# SPosition.net
KiCad netlist of a schematic drawn in EAGLE
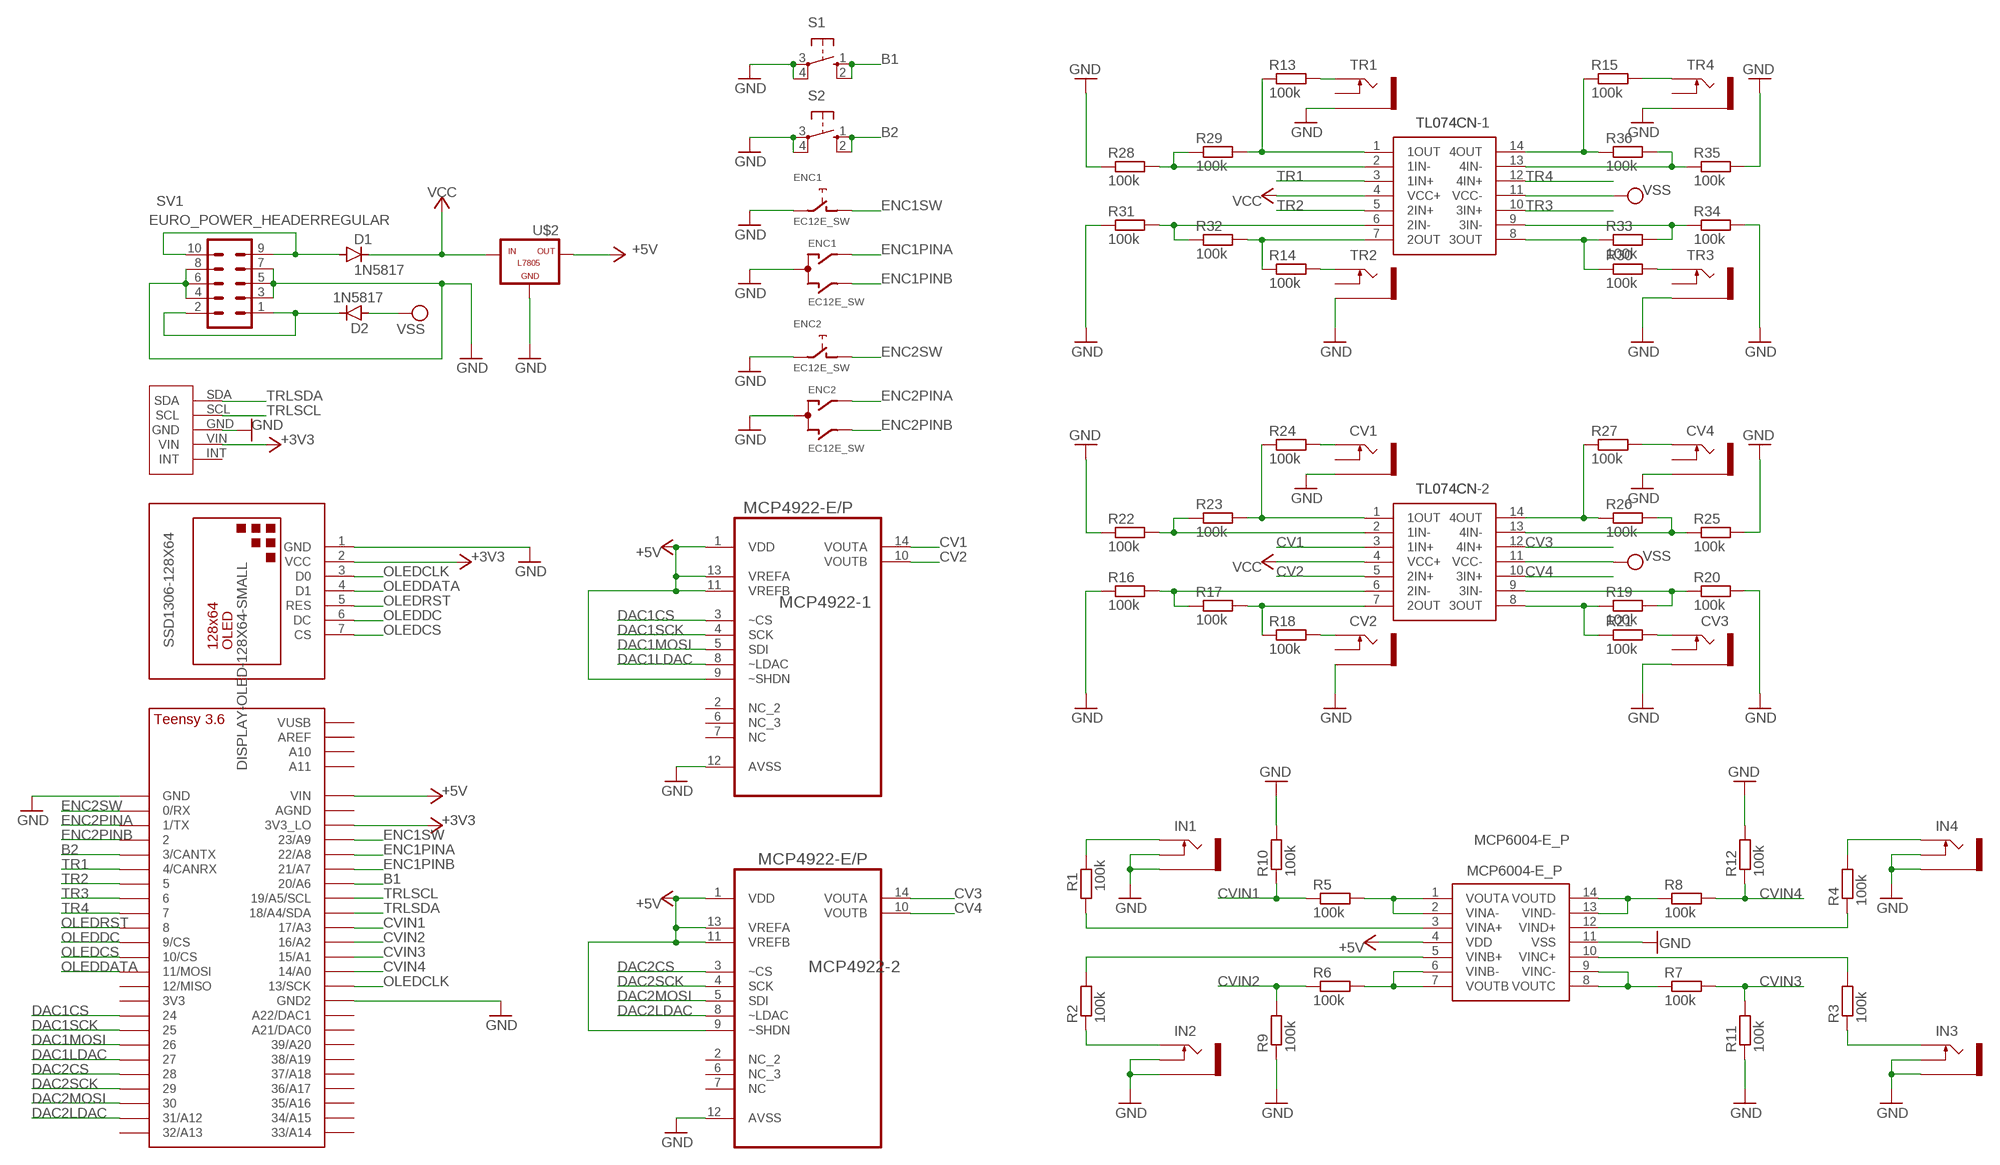
[diagram p0: schematic, sheet 1]

(export (version "E")
  (design (tool "Eeschema 10.0.6"))
  (components
    (comp (ref "CV1")
      (value "THONKICONNNEW")
      (footprint "eagle-import:WQP-PJ301M-12_JACK")
      (libsource (lib "eagle-import") (part "THONKICONNNEW"))
    )
    (comp (ref "CV2")
      (value "THONKICONNNEW")
      (footprint "eagle-import:WQP-PJ301M-12_JACK")
      (libsource (lib "eagle-import") (part "THONKICONNNEW"))
    )
    (comp (ref "CV3")
      (value "THONKICONNNEW")
      (footprint "eagle-import:WQP-PJ301M-12_JACK")
      (libsource (lib "eagle-import") (part "THONKICONNNEW"))
    )
    (comp (ref "CV4")
      (value "THONKICONNNEW")
      (footprint "eagle-import:WQP-PJ301M-12_JACK")
      (libsource (lib "eagle-import") (part "THONKICONNNEW"))
    )
    (comp (ref "D1")
      (value "1N5817")
      (footprint "eagle-import:DO41-10")
      (libsource (lib "eagle-import") (part "1N4004"))
    )
    (comp (ref "D2")
      (value "1N5817")
      (footprint "eagle-import:DO41-10")
      (libsource (lib "eagle-import") (part "1N4004"))
    )
    (comp (ref "ENC1")
      (value "EC12E_SW")
      (footprint "eagle-import:ALPS_EC12E_SW")
      (fields (field (name "MPN") "EC12E2424407"))
      (libsource (lib "eagle-import") (part "EC12E_SW"))
    )
    (comp (ref "ENC2")
      (value "EC12E_SW")
      (footprint "eagle-import:ALPS_EC12E_SW")
      (fields (field (name "MPN") "EC12E2424407"))
      (libsource (lib "eagle-import") (part "EC12E_SW"))
    )
    (comp (ref "IN1")
      (value "THONKICONNNEW")
      (footprint "eagle-import:WQP-PJ301M-12_JACK")
      (libsource (lib "eagle-import") (part "THONKICONNNEW"))
    )
    (comp (ref "IN2")
      (value "THONKICONNNEW")
      (footprint "eagle-import:WQP-PJ301M-12_JACK")
      (libsource (lib "eagle-import") (part "THONKICONNNEW"))
    )
    (comp (ref "IN3")
      (value "THONKICONNNEW")
      (footprint "eagle-import:WQP-PJ301M-12_JACK")
      (libsource (lib "eagle-import") (part "THONKICONNNEW"))
    )
    (comp (ref "IN4")
      (value "THONKICONNNEW")
      (footprint "eagle-import:WQP-PJ301M-12_JACK")
      (libsource (lib "eagle-import") (part "THONKICONNNEW"))
    )
    (comp (ref "MCP4922-1")
      (value "MCP4922-E/P")
      (footprint "eagle-import:DIP254P762X533-14")
      (fields (field (name "MF") "Microchip"))
      (libsource (lib "eagle-import") (part "MCP4922-E/P"))
    )
    (comp (ref "MCP4922-2")
      (value "MCP4922-E/P")
      (footprint "eagle-import:DIP254P762X533-14")
      (fields (field (name "MF") "Microchip"))
      (libsource (lib "eagle-import") (part "MCP4922-E/P"))
    )
    (comp (ref "MCP6004-E_P")
      (value "MCP6004-E_P")
      (footprint "eagle-import:DIP781W56P254L1918H533Q14N")
      (fields
        (field (name "MANUFACTURER_PART_NUMBER") "mcp6004-e/p")
        (field (name "MOUSER_PART_NUMBER") "579-MCP6004-E/P")
        (field (name "RS_PART_NUMBER") "7386178P")
      )
      (libsource (lib "eagle-import") (part "MCP6004-E_P"))
    )
    (comp (ref "R1")
      (value "100k")
      (footprint "eagle-import:R0805")
      (libsource (lib "eagle-import") (part "R-EU_R0805"))
    )
    (comp (ref "R2")
      (value "100k")
      (footprint "eagle-import:R0805")
      (libsource (lib "eagle-import") (part "R-EU_R0805"))
    )
    (comp (ref "R3")
      (value "100k")
      (footprint "eagle-import:R0805")
      (libsource (lib "eagle-import") (part "R-EU_R0805"))
    )
    (comp (ref "R4")
      (value "100k")
      (footprint "eagle-import:R0805")
      (libsource (lib "eagle-import") (part "R-EU_R0805"))
    )
    (comp (ref "R5")
      (value "100k")
      (footprint "eagle-import:R0805")
      (libsource (lib "eagle-import") (part "R-EU_R0805"))
    )
    (comp (ref "R6")
      (value "100k")
      (footprint "eagle-import:R0805")
      (libsource (lib "eagle-import") (part "R-EU_R0805"))
    )
    (comp (ref "R7")
      (value "100k")
      (footprint "eagle-import:R0805")
      (libsource (lib "eagle-import") (part "R-EU_R0805"))
    )
    (comp (ref "R8")
      (value "100k")
      (footprint "eagle-import:R0805")
      (libsource (lib "eagle-import") (part "R-EU_R0805"))
    )
    (comp (ref "R9")
      (value "100k")
      (footprint "eagle-import:R0805")
      (libsource (lib "eagle-import") (part "R-EU_R0805"))
    )
    (comp (ref "R10")
      (value "100k")
      (footprint "eagle-import:R0805")
      (libsource (lib "eagle-import") (part "R-EU_R0805"))
    )
    (comp (ref "R11")
      (value "100k")
      (footprint "eagle-import:R0805")
      (libsource (lib "eagle-import") (part "R-EU_R0805"))
    )
    (comp (ref "R12")
      (value "100k")
      (footprint "eagle-import:R0805")
      (libsource (lib "eagle-import") (part "R-EU_R0805"))
    )
    (comp (ref "R13")
      (value "100k")
      (footprint "eagle-import:R0805")
      (libsource (lib "eagle-import") (part "R-EU_R0805"))
    )
    (comp (ref "R14")
      (value "100k")
      (footprint "eagle-import:R0805")
      (libsource (lib "eagle-import") (part "R-EU_R0805"))
    )
    (comp (ref "R15")
      (value "100k")
      (footprint "eagle-import:R0805")
      (libsource (lib "eagle-import") (part "R-EU_R0805"))
    )
    (comp (ref "R16")
      (value "100k")
      (footprint "eagle-import:R0805")
      (libsource (lib "eagle-import") (part "R-EU_R0805"))
    )
    (comp (ref "R17")
      (value "100k")
      (footprint "eagle-import:R0805")
      (libsource (lib "eagle-import") (part "R-EU_R0805"))
    )
    (comp (ref "R18")
      (value "100k")
      (footprint "eagle-import:R0805")
      (libsource (lib "eagle-import") (part "R-EU_R0805"))
    )
    (comp (ref "R19")
      (value "100k")
      (footprint "eagle-import:R0805")
      (libsource (lib "eagle-import") (part "R-EU_R0805"))
    )
    (comp (ref "R20")
      (value "100k")
      (footprint "eagle-import:R0805")
      (libsource (lib "eagle-import") (part "R-EU_R0805"))
    )
    (comp (ref "R21")
      (value "100k")
      (footprint "eagle-import:R0805")
      (libsource (lib "eagle-import") (part "R-EU_R0805"))
    )
    (comp (ref "R22")
      (value "100k")
      (footprint "eagle-import:R0805")
      (libsource (lib "eagle-import") (part "R-EU_R0805"))
    )
    (comp (ref "R23")
      (value "100k")
      (footprint "eagle-import:R0805")
      (libsource (lib "eagle-import") (part "R-EU_R0805"))
    )
    (comp (ref "R24")
      (value "100k")
      (footprint "eagle-import:R0805")
      (libsource (lib "eagle-import") (part "R-EU_R0805"))
    )
    (comp (ref "R25")
      (value "100k")
      (footprint "eagle-import:R0805")
      (libsource (lib "eagle-import") (part "R-EU_R0805"))
    )
    (comp (ref "R26")
      (value "100k")
      (footprint "eagle-import:R0805")
      (libsource (lib "eagle-import") (part "R-EU_R0805"))
    )
    (comp (ref "R27")
      (value "100k")
      (footprint "eagle-import:R0805")
      (libsource (lib "eagle-import") (part "R-EU_R0805"))
    )
    (comp (ref "R28")
      (value "100k")
      (footprint "eagle-import:R0805")
      (libsource (lib "eagle-import") (part "R-EU_R0805"))
    )
    (comp (ref "R29")
      (value "100k")
      (footprint "eagle-import:R0805")
      (libsource (lib "eagle-import") (part "R-EU_R0805"))
    )
    (comp (ref "R30")
      (value "100k")
      (footprint "eagle-import:R0805")
      (libsource (lib "eagle-import") (part "R-EU_R0805"))
    )
    (comp (ref "R31")
      (value "100k")
      (footprint "eagle-import:R0805")
      (libsource (lib "eagle-import") (part "R-EU_R0805"))
    )
    (comp (ref "R32")
      (value "100k")
      (footprint "eagle-import:R0805")
      (libsource (lib "eagle-import") (part "R-EU_R0805"))
    )
    (comp (ref "R33")
      (value "100k")
      (footprint "eagle-import:R0805")
      (libsource (lib "eagle-import") (part "R-EU_R0805"))
    )
    (comp (ref "R34")
      (value "100k")
      (footprint "eagle-import:R0805")
      (libsource (lib "eagle-import") (part "R-EU_R0805"))
    )
    (comp (ref "R35")
      (value "100k")
      (footprint "eagle-import:R0805")
      (libsource (lib "eagle-import") (part "R-EU_R0805"))
    )
    (comp (ref "R36")
      (value "100k")
      (footprint "eagle-import:R0805")
      (libsource (lib "eagle-import") (part "R-EU_R0805"))
    )
    (comp (ref "S1")
      (value "10-XX")
      (footprint "eagle-import:B3F-10XX")
      (fields (field (name "MPN") "B3F-1000"))
      (libsource (lib "eagle-import") (part "10-XX"))
    )
    (comp (ref "S2")
      (value "10-XX")
      (footprint "eagle-import:B3F-10XX")
      (fields (field (name "MPN") "B3F-1000"))
      (libsource (lib "eagle-import") (part "10-XX"))
    )
    (comp (ref "SSD1306-128X64")
      (value "DISPLAY-OLED-128X64-SMALL")
      (footprint "eagle-import:DISPLAY-OLED-128X64-SMALL")
      (libsource (lib "eagle-import") (part "DISPLAY-OLED-128X64-SMALL"))
    )
    (comp (ref "SV1")
      (value "EURO_POWER_HEADERREGULAR")
      (footprint "eagle-import:EURO_POWER_HEADER")
      (libsource (lib "eagle-import") (part "EURO_POWER_HEADERREGULAR"))
    )
    (comp (ref "TL074CN-1")
      (value "TL074CN")
      (footprint "eagle-import:DIP794W53P254L1930H508Q14N")
      (fields (field (name "MOUSER_PART_NUMBER") "595-TL074CN") (field (name "RS_PART_NUMBER") "0302621P"))
      (libsource (lib "eagle-import") (part "TL074CN"))
    )
    (comp (ref "TL074CN-2")
      (value "TL074CN")
      (footprint "eagle-import:DIP794W53P254L1930H508Q14N")
      (fields (field (name "MOUSER_PART_NUMBER") "595-TL074CN") (field (name "RS_PART_NUMBER") "0302621P"))
      (libsource (lib "eagle-import") (part "TL074CN"))
    )
    (comp (ref "TR1")
      (value "THONKICONNNEW")
      (footprint "eagle-import:WQP-PJ301M-12_JACK")
      (libsource (lib "eagle-import") (part "THONKICONNNEW"))
    )
    (comp (ref "TR2")
      (value "THONKICONNNEW")
      (footprint "eagle-import:WQP-PJ301M-12_JACK")
      (libsource (lib "eagle-import") (part "THONKICONNNEW"))
    )
    (comp (ref "TR3")
      (value "THONKICONNNEW")
      (footprint "eagle-import:WQP-PJ301M-12_JACK")
      (libsource (lib "eagle-import") (part "THONKICONNNEW"))
    )
    (comp (ref "TR4")
      (value "THONKICONNNEW")
      (footprint "eagle-import:WQP-PJ301M-12_JACK")
      (libsource (lib "eagle-import") (part "THONKICONNNEW"))
    )
    (comp (ref "U$1")
      (value "TEENSY_3.5/3.6_BASIC")
      (footprint "eagle-import:TEENSY_3.5_3.6_BASIC")
      (libsource (lib "eagle-import") (part "TEENSY_3.5/3.6_BASIC"))
    )
    (comp (ref "U$2")
      (value "-L7805")
      (footprint "eagle-import:L7805")
      (libsource (lib "eagle-import") (part "-L7805"))
    )
    (comp (ref "U$4")
      (value "SPREV3")
      (footprint "eagle-import:SPREV3")
      (libsource (lib "eagle-import") (part "SPREV3"))
    )
  )
  (nets
    (net (code "1") (name "+3V3") (class "Default")
      (node (ref "SSD1306-128X64") (pin "2") (pinfunction "VCC_2") (pintype "power_in"))
      (node (ref "U$1") (pin "3V3_LO") (pinfunction "3V3_LO_3V3_LO") (pintype "bidirectional"))
      (node (ref "U$4") (pin "VIN") (pinfunction "VIN_VIN") (pintype "bidirectional"))
    )
    (net (code "2") (name "+5V") (class "Default")
      (node (ref "MCP4922-1") (pin "1") (pinfunction "VDD_1") (pintype "power_in"))
      (node (ref "MCP4922-1") (pin "11") (pinfunction "VREFB_11") (pintype "input"))
      (node (ref "MCP4922-1") (pin "13") (pinfunction "VREFA_13") (pintype "input"))
      (node (ref "MCP4922-1") (pin "9") (pinfunction "~{SHDN}_9") (pintype "input"))
      (node (ref "MCP4922-2") (pin "1") (pinfunction "VDD_1") (pintype "power_in"))
      (node (ref "MCP4922-2") (pin "11") (pinfunction "VREFB_11") (pintype "input"))
      (node (ref "MCP4922-2") (pin "13") (pinfunction "VREFA_13") (pintype "input"))
      (node (ref "MCP4922-2") (pin "9") (pinfunction "~{SHDN}_9") (pintype "input"))
      (node (ref "MCP6004-E_P") (pin "4") (pinfunction "VDD_4") (pintype "power_in"))
      (node (ref "U$1") (pin "VIN") (pinfunction "VIN_VIN") (pintype "bidirectional"))
      (node (ref "U$2") (pin "OUT") (pinfunction "OUT_OUT") (pintype "passive"))
    )
    (net (code "3") (name "/B1") (class "Default")
      (node (ref "S1") (pin "1") (pinfunction "S_1") (pintype "passive"))
      (node (ref "S1") (pin "2") (pinfunction "S1_2") (pintype "passive"))
      (node (ref "U$1") (pin "20/A6") (pinfunction "20/A6_20/A6") (pintype "bidirectional"))
    )
    (net (code "4") (name "/B2") (class "Default")
      (node (ref "S2") (pin "1") (pinfunction "S_1") (pintype "passive"))
      (node (ref "S2") (pin "2") (pinfunction "S1_2") (pintype "passive"))
      (node (ref "U$1") (pin "3/CANTX") (pinfunction "3/CANTX_3/CANTX") (pintype "bidirectional"))
    )
    (net (code "5") (name "/CV1") (class "Default")
      (node (ref "MCP4922-1") (pin "14") (pinfunction "VOUTA_14") (pintype "output"))
      (node (ref "TL074CN-2") (pin "3") (pinfunction "1IN+_3") (pintype "input"))
    )
    (net (code "6") (name "/CV2") (class "Default")
      (node (ref "MCP4922-1") (pin "10") (pinfunction "VOUTB_10") (pintype "output"))
      (node (ref "TL074CN-2") (pin "5") (pinfunction "2IN+_5") (pintype "input"))
    )
    (net (code "7") (name "/CV3") (class "Default")
      (node (ref "MCP4922-2") (pin "14") (pinfunction "VOUTA_14") (pintype "output"))
      (node (ref "TL074CN-2") (pin "12") (pinfunction "4IN+_12") (pintype "input"))
    )
    (net (code "8") (name "/CV4") (class "Default")
      (node (ref "MCP4922-2") (pin "10") (pinfunction "VOUTB_10") (pintype "output"))
      (node (ref "TL074CN-2") (pin "10") (pinfunction "3IN+_10") (pintype "input"))
    )
    (net (code "9") (name "/CVIN1") (class "Default")
      (node (ref "R10") (pin "1") (pinfunction "1_1") (pintype "passive"))
      (node (ref "R5") (pin "1") (pinfunction "1_1") (pintype "passive"))
      (node (ref "U$1") (pin "17/A3") (pinfunction "17/A3_17/A3") (pintype "bidirectional"))
    )
    (net (code "10") (name "/CVIN2") (class "Default")
      (node (ref "R6") (pin "1") (pinfunction "1_1") (pintype "passive"))
      (node (ref "R9") (pin "2") (pinfunction "2_2") (pintype "passive"))
      (node (ref "U$1") (pin "16/A2") (pinfunction "16/A2_16/A2") (pintype "bidirectional"))
    )
    (net (code "11") (name "/CVIN3") (class "Default")
      (node (ref "R11") (pin "2") (pinfunction "2_2") (pintype "passive"))
      (node (ref "R7") (pin "2") (pinfunction "2_2") (pintype "passive"))
      (node (ref "U$1") (pin "15/A1") (pinfunction "15/A1_15/A1") (pintype "bidirectional"))
    )
    (net (code "12") (name "/CVIN4") (class "Default")
      (node (ref "R12") (pin "1") (pinfunction "1_1") (pintype "passive"))
      (node (ref "R8") (pin "2") (pinfunction "2_2") (pintype "passive"))
      (node (ref "U$1") (pin "14/A0") (pinfunction "14/A0_14/A0") (pintype "bidirectional"))
    )
    (net (code "13") (name "/DAC1CS") (class "Default")
      (node (ref "MCP4922-1") (pin "3") (pinfunction "~{CS}_3") (pintype "input"))
      (node (ref "U$1") (pin "24") (pinfunction "24_24") (pintype "bidirectional"))
    )
    (net (code "14") (name "/DAC1LDAC") (class "Default")
      (node (ref "MCP4922-1") (pin "8") (pinfunction "~{LDAC}_8") (pintype "input"))
      (node (ref "U$1") (pin "27") (pinfunction "27_27") (pintype "bidirectional"))
    )
    (net (code "15") (name "/DAC1MOSI") (class "Default")
      (node (ref "MCP4922-1") (pin "5") (pinfunction "SDI_5") (pintype "input"))
      (node (ref "U$1") (pin "26") (pinfunction "26_26") (pintype "bidirectional"))
    )
    (net (code "16") (name "/DAC1SCK") (class "Default")
      (node (ref "MCP4922-1") (pin "4") (pinfunction "SCK_4") (pintype "input"))
      (node (ref "U$1") (pin "25") (pinfunction "25_25") (pintype "bidirectional"))
    )
    (net (code "17") (name "/DAC2CS") (class "Default")
      (node (ref "MCP4922-2") (pin "3") (pinfunction "~{CS}_3") (pintype "input"))
      (node (ref "U$1") (pin "28") (pinfunction "28_28") (pintype "bidirectional"))
    )
    (net (code "18") (name "/DAC2LDAC") (class "Default")
      (node (ref "MCP4922-2") (pin "8") (pinfunction "~{LDAC}_8") (pintype "input"))
      (node (ref "U$1") (pin "31/A12") (pinfunction "31/A12_31/A12") (pintype "bidirectional"))
    )
    (net (code "19") (name "/DAC2MOSI") (class "Default")
      (node (ref "MCP4922-2") (pin "5") (pinfunction "SDI_5") (pintype "input"))
      (node (ref "U$1") (pin "30") (pinfunction "30_30") (pintype "bidirectional"))
    )
    (net (code "20") (name "/DAC2SCK") (class "Default")
      (node (ref "MCP4922-2") (pin "4") (pinfunction "SCK_4") (pintype "input"))
      (node (ref "U$1") (pin "29") (pinfunction "29_29") (pintype "bidirectional"))
    )
    (net (code "21") (name "/ENC1PINA") (class "Default")
      (node (ref "ENC1") (pin "A") (pinfunction "A_A") (pintype "passive"))
      (node (ref "U$1") (pin "22/A8") (pinfunction "22/A8_22/A8") (pintype "bidirectional"))
    )
    (net (code "22") (name "/ENC1PINB") (class "Default")
      (node (ref "ENC1") (pin "B") (pinfunction "B_B") (pintype "passive"))
      (node (ref "U$1") (pin "21/A7") (pinfunction "21/A7_21/A7") (pintype "bidirectional"))
    )
    (net (code "23") (name "/ENC1SW") (class "Default")
      (node (ref "ENC1") (pin "D") (pinfunction "1_D") (pintype "passive"))
      (node (ref "U$1") (pin "23/A9") (pinfunction "23/A9_23/A9") (pintype "bidirectional"))
    )
    (net (code "24") (name "/ENC2PINA") (class "Default")
      (node (ref "ENC2") (pin "A") (pinfunction "A_A") (pintype "passive"))
      (node (ref "U$1") (pin "1/TX") (pinfunction "1/TX_1/TX") (pintype "bidirectional"))
    )
    (net (code "25") (name "/ENC2PINB") (class "Default")
      (node (ref "ENC2") (pin "B") (pinfunction "B_B") (pintype "passive"))
      (node (ref "U$1") (pin "2") (pinfunction "2_2") (pintype "bidirectional"))
    )
    (net (code "26") (name "/ENC2SW") (class "Default")
      (node (ref "ENC2") (pin "D") (pinfunction "1_D") (pintype "passive"))
      (node (ref "U$1") (pin "0/RX") (pinfunction "0/RX_0/RX") (pintype "bidirectional"))
    )
    (net (code "27") (name "/OLEDCLK") (class "Default")
      (node (ref "SSD1306-128X64") (pin "3") (pinfunction "D0_3") (pintype "bidirectional"))
      (node (ref "U$1") (pin "13/SCK") (pinfunction "13/SCK_13/SCK") (pintype "bidirectional"))
    )
    (net (code "28") (name "/OLEDCS") (class "Default")
      (node (ref "SSD1306-128X64") (pin "7") (pinfunction "CS_7") (pintype "bidirectional"))
      (node (ref "U$1") (pin "10/CS") (pinfunction "10/CS_10/CS") (pintype "bidirectional"))
    )
    (net (code "29") (name "/OLEDDATA") (class "Default")
      (node (ref "SSD1306-128X64") (pin "4") (pinfunction "D1_4") (pintype "bidirectional"))
      (node (ref "U$1") (pin "11/MOSI") (pinfunction "11/MOSI_11/MOSI") (pintype "bidirectional"))
    )
    (net (code "30") (name "/OLEDDC") (class "Default")
      (node (ref "SSD1306-128X64") (pin "6") (pinfunction "DC_6") (pintype "bidirectional"))
      (node (ref "U$1") (pin "9/CS") (pinfunction "9/CS_9/CS") (pintype "bidirectional"))
    )
    (net (code "31") (name "/OLEDRST") (class "Default")
      (node (ref "SSD1306-128X64") (pin "5") (pinfunction "RES_5") (pintype "bidirectional"))
      (node (ref "U$1") (pin "8") (pinfunction "8_8") (pintype "bidirectional"))
    )
    (net (code "32") (name "/TR1") (class "Default")
      (node (ref "TL074CN-1") (pin "3") (pinfunction "1IN+_3") (pintype "input"))
      (node (ref "U$1") (pin "4/CANRX") (pinfunction "4/CANRX_4/CANRX") (pintype "bidirectional"))
    )
    (net (code "33") (name "/TR2") (class "Default")
      (node (ref "TL074CN-1") (pin "5") (pinfunction "2IN+_5") (pintype "input"))
      (node (ref "U$1") (pin "5") (pinfunction "5_5") (pintype "bidirectional"))
    )
    (net (code "34") (name "/TR3") (class "Default")
      (node (ref "TL074CN-1") (pin "10") (pinfunction "3IN+_10") (pintype "input"))
      (node (ref "U$1") (pin "6") (pinfunction "6_6") (pintype "bidirectional"))
    )
    (net (code "35") (name "/TR4") (class "Default")
      (node (ref "TL074CN-1") (pin "12") (pinfunction "4IN+_12") (pintype "input"))
      (node (ref "U$1") (pin "7") (pinfunction "7_7") (pintype "bidirectional"))
    )
    (net (code "36") (name "/TRLSCL") (class "Default")
      (node (ref "U$1") (pin "19/A5/SCL") (pinfunction "19/A5/SCL_19/A5/SCL") (pintype "bidirectional"))
      (node (ref "U$4") (pin "SCL") (pinfunction "SCL_SCL") (pintype "bidirectional"))
    )
    (net (code "37") (name "/TRLSDA") (class "Default")
      (node (ref "U$1") (pin "18/A4/SDA") (pinfunction "18/A4/SDA_18/A4/SDA") (pintype "bidirectional"))
      (node (ref "U$4") (pin "SDA") (pinfunction "SDA_SDA") (pintype "bidirectional"))
    )
    (net (code "38") (name "GND") (class "Default")
      (node (ref "CV1") (pin "P$3_SLEEVE") (pinfunction "SLEEVE_P$3_SLEEVE") (pintype "passive"))
      (node (ref "CV2") (pin "P$3_SLEEVE") (pinfunction "SLEEVE_P$3_SLEEVE") (pintype "passive"))
      (node (ref "CV3") (pin "P$3_SLEEVE") (pinfunction "SLEEVE_P$3_SLEEVE") (pintype "passive"))
      (node (ref "CV4") (pin "P$3_SLEEVE") (pinfunction "SLEEVE_P$3_SLEEVE") (pintype "passive"))
      (node (ref "ENC1") (pin "C") (pinfunction "C_C") (pintype "passive"))
      (node (ref "ENC1") (pin "E") (pinfunction "2_E") (pintype "passive"))
      (node (ref "ENC2") (pin "C") (pinfunction "C_C") (pintype "passive"))
      (node (ref "ENC2") (pin "E") (pinfunction "2_E") (pintype "passive"))
      (node (ref "IN1") (pin "P$2_SWITCH") (pinfunction "SWITCH_P$2_SWITCH") (pintype "passive"))
      (node (ref "IN1") (pin "P$3_SLEEVE") (pinfunction "SLEEVE_P$3_SLEEVE") (pintype "passive"))
      (node (ref "IN2") (pin "P$2_SWITCH") (pinfunction "SWITCH_P$2_SWITCH") (pintype "passive"))
      (node (ref "IN2") (pin "P$3_SLEEVE") (pinfunction "SLEEVE_P$3_SLEEVE") (pintype "passive"))
      (node (ref "IN3") (pin "P$2_SWITCH") (pinfunction "SWITCH_P$2_SWITCH") (pintype "passive"))
      (node (ref "IN3") (pin "P$3_SLEEVE") (pinfunction "SLEEVE_P$3_SLEEVE") (pintype "passive"))
      (node (ref "IN4") (pin "P$2_SWITCH") (pinfunction "SWITCH_P$2_SWITCH") (pintype "passive"))
      (node (ref "IN4") (pin "P$3_SLEEVE") (pinfunction "SLEEVE_P$3_SLEEVE") (pintype "passive"))
      (node (ref "MCP4922-1") (pin "12") (pinfunction "AVSS_12") (pintype "power_in"))
      (node (ref "MCP4922-2") (pin "12") (pinfunction "AVSS_12") (pintype "power_in"))
      (node (ref "MCP6004-E_P") (pin "11") (pinfunction "VSS_11") (pintype "power_in"))
      (node (ref "R10") (pin "2") (pinfunction "2_2") (pintype "passive"))
      (node (ref "R11") (pin "1") (pinfunction "1_1") (pintype "passive"))
      (node (ref "R12") (pin "2") (pinfunction "2_2") (pintype "passive"))
      (node (ref "R16") (pin "1") (pinfunction "1_1") (pintype "passive"))
      (node (ref "R20") (pin "2") (pinfunction "2_2") (pintype "passive"))
      (node (ref "R22") (pin "1") (pinfunction "1_1") (pintype "passive"))
      (node (ref "R25") (pin "2") (pinfunction "2_2") (pintype "passive"))
      (node (ref "R28") (pin "1") (pinfunction "1_1") (pintype "passive"))
      (node (ref "R31") (pin "1") (pinfunction "1_1") (pintype "passive"))
      (node (ref "R34") (pin "2") (pinfunction "2_2") (pintype "passive"))
      (node (ref "R35") (pin "2") (pinfunction "2_2") (pintype "passive"))
      (node (ref "R9") (pin "1") (pinfunction "1_1") (pintype "passive"))
      (node (ref "S1") (pin "3") (pinfunction "P_3") (pintype "passive"))
      (node (ref "S1") (pin "4") (pinfunction "P1_4") (pintype "passive"))
      (node (ref "S2") (pin "3") (pinfunction "P_3") (pintype "passive"))
      (node (ref "S2") (pin "4") (pinfunction "P1_4") (pintype "passive"))
      (node (ref "SSD1306-128X64") (pin "1") (pinfunction "GND_1") (pintype "power_in"))
      (node (ref "SV1") (pin "3") (pinfunction "3_3") (pintype "passive"))
      (node (ref "SV1") (pin "4") (pinfunction "4_4") (pintype "passive"))
      (node (ref "SV1") (pin "5") (pinfunction "5_5") (pintype "passive"))
      (node (ref "SV1") (pin "6") (pinfunction "6_6") (pintype "passive"))
      (node (ref "SV1") (pin "7") (pinfunction "7_7") (pintype "passive"))
      (node (ref "SV1") (pin "8") (pinfunction "8_8") (pintype "passive"))
      (node (ref "TR1") (pin "P$3_SLEEVE") (pinfunction "SLEEVE_P$3_SLEEVE") (pintype "passive"))
      (node (ref "TR2") (pin "P$3_SLEEVE") (pinfunction "SLEEVE_P$3_SLEEVE") (pintype "passive"))
      (node (ref "TR3") (pin "P$3_SLEEVE") (pinfunction "SLEEVE_P$3_SLEEVE") (pintype "passive"))
      (node (ref "TR4") (pin "P$3_SLEEVE") (pinfunction "SLEEVE_P$3_SLEEVE") (pintype "passive"))
      (node (ref "U$1") (pin "GND") (pinfunction "GND_GND") (pintype "bidirectional"))
      (node (ref "U$1") (pin "GND2") (pinfunction "GND2_GND2") (pintype "bidirectional"))
      (node (ref "U$2") (pin "GND") (pinfunction "GND_GND") (pintype "input"))
      (node (ref "U$4") (pin "GND") (pinfunction "GND_GND") (pintype "bidirectional"))
    )
    (net (code "39") (name "Net-(CV1-TIP)") (class "Default")
      (node (ref "CV1") (pin "P$1_TIP") (pinfunction "TIP_P$1_TIP") (pintype "passive"))
      (node (ref "R24") (pin "2") (pinfunction "2_2") (pintype "passive"))
    )
    (net (code "40") (name "Net-(CV2-TIP)") (class "Default")
      (node (ref "CV2") (pin "P$1_TIP") (pinfunction "TIP_P$1_TIP") (pintype "passive"))
      (node (ref "R18") (pin "2") (pinfunction "2_2") (pintype "passive"))
    )
    (net (code "41") (name "Net-(CV3-TIP)") (class "Default")
      (node (ref "CV3") (pin "P$1_TIP") (pinfunction "TIP_P$1_TIP") (pintype "passive"))
      (node (ref "R21") (pin "2") (pinfunction "2_2") (pintype "passive"))
    )
    (net (code "42") (name "Net-(CV4-TIP)") (class "Default")
      (node (ref "CV4") (pin "P$1_TIP") (pinfunction "TIP_P$1_TIP") (pintype "passive"))
      (node (ref "R27") (pin "2") (pinfunction "2_2") (pintype "passive"))
    )
    (net (code "43") (name "Net-(D1-PadA)") (class "Default")
      (node (ref "D1") (pin "A") (pinfunction "A_A") (pintype "passive"))
      (node (ref "SV1") (pin "10") (pinfunction "10_10") (pintype "passive"))
      (node (ref "SV1") (pin "9") (pinfunction "9_9") (pintype "passive"))
    )
    (net (code "44") (name "Net-(D2-PadC)") (class "Default")
      (node (ref "D2") (pin "C") (pinfunction "C_C") (pintype "passive"))
      (node (ref "SV1") (pin "1") (pinfunction "1_1") (pintype "passive"))
      (node (ref "SV1") (pin "2") (pinfunction "2_2") (pintype "passive"))
    )
    (net (code "45") (name "Net-(IN1-TIP)") (class "Default")
      (node (ref "IN1") (pin "P$1_TIP") (pinfunction "TIP_P$1_TIP") (pintype "passive"))
      (node (ref "R1") (pin "2") (pinfunction "2_2") (pintype "passive"))
    )
    (net (code "46") (name "Net-(IN2-TIP)") (class "Default")
      (node (ref "IN2") (pin "P$1_TIP") (pinfunction "TIP_P$1_TIP") (pintype "passive"))
      (node (ref "R2") (pin "1") (pinfunction "1_1") (pintype "passive"))
    )
    (net (code "47") (name "Net-(IN3-TIP)") (class "Default")
      (node (ref "IN3") (pin "P$1_TIP") (pinfunction "TIP_P$1_TIP") (pintype "passive"))
      (node (ref "R3") (pin "1") (pinfunction "1_1") (pintype "passive"))
    )
    (net (code "48") (name "Net-(IN4-TIP)") (class "Default")
      (node (ref "IN4") (pin "P$1_TIP") (pinfunction "TIP_P$1_TIP") (pintype "passive"))
      (node (ref "R4") (pin "2") (pinfunction "2_2") (pintype "passive"))
    )
    (net (code "49") (name "Net-(MCP6004-E_P-VINA+)") (class "Default")
      (node (ref "MCP6004-E_P") (pin "3") (pinfunction "VINA+_3") (pintype "input"))
      (node (ref "R1") (pin "1") (pinfunction "1_1") (pintype "passive"))
    )
    (net (code "50") (name "Net-(MCP6004-E_P-VINA-)") (class "Default")
      (node (ref "MCP6004-E_P") (pin "1") (pinfunction "VOUTA_1") (pintype "output"))
      (node (ref "MCP6004-E_P") (pin "2") (pinfunction "VINA-_2") (pintype "input"))
      (node (ref "R5") (pin "2") (pinfunction "2_2") (pintype "passive"))
    )
    (net (code "51") (name "Net-(MCP6004-E_P-VINB+)") (class "Default")
      (node (ref "MCP6004-E_P") (pin "5") (pinfunction "VINB+_5") (pintype "input"))
      (node (ref "R2") (pin "2") (pinfunction "2_2") (pintype "passive"))
    )
    (net (code "52") (name "Net-(MCP6004-E_P-VINB-)") (class "Default")
      (node (ref "MCP6004-E_P") (pin "6") (pinfunction "VINB-_6") (pintype "input"))
      (node (ref "MCP6004-E_P") (pin "7") (pinfunction "VOUTB_7") (pintype "output"))
      (node (ref "R6") (pin "2") (pinfunction "2_2") (pintype "passive"))
    )
    (net (code "53") (name "Net-(MCP6004-E_P-VINC+)") (class "Default")
      (node (ref "MCP6004-E_P") (pin "10") (pinfunction "VINC+_10") (pintype "input"))
      (node (ref "R3") (pin "2") (pinfunction "2_2") (pintype "passive"))
    )
    (net (code "54") (name "Net-(MCP6004-E_P-VINC-)") (class "Default")
      (node (ref "MCP6004-E_P") (pin "8") (pinfunction "VOUTC_8") (pintype "output"))
      (node (ref "MCP6004-E_P") (pin "9") (pinfunction "VINC-_9") (pintype "input"))
      (node (ref "R7") (pin "1") (pinfunction "1_1") (pintype "passive"))
    )
    (net (code "55") (name "Net-(MCP6004-E_P-VIND+)") (class "Default")
      (node (ref "MCP6004-E_P") (pin "12") (pinfunction "VIND+_12") (pintype "input"))
      (node (ref "R4") (pin "1") (pinfunction "1_1") (pintype "passive"))
    )
    (net (code "56") (name "Net-(MCP6004-E_P-VIND-)") (class "Default")
      (node (ref "MCP6004-E_P") (pin "13") (pinfunction "VIND-_13") (pintype "input"))
      (node (ref "MCP6004-E_P") (pin "14") (pinfunction "VOUTD_14") (pintype "output"))
      (node (ref "R8") (pin "1") (pinfunction "1_1") (pintype "passive"))
    )
    (net (code "57") (name "Net-(TL074CN-1-1IN-)") (class "Default")
      (node (ref "R28") (pin "2") (pinfunction "2_2") (pintype "passive"))
      (node (ref "R29") (pin "1") (pinfunction "1_1") (pintype "passive"))
      (node (ref "TL074CN-1") (pin "2") (pinfunction "1IN-_2") (pintype "input"))
    )
    (net (code "58") (name "Net-(TL074CN-1-1OUT)") (class "Default")
      (node (ref "R13") (pin "1") (pinfunction "1_1") (pintype "passive"))
      (node (ref "R29") (pin "2") (pinfunction "2_2") (pintype "passive"))
      (node (ref "TL074CN-1") (pin "1") (pinfunction "1OUT_1") (pintype "output"))
    )
    (net (code "59") (name "Net-(TL074CN-1-2IN-)") (class "Default")
      (node (ref "R31") (pin "2") (pinfunction "2_2") (pintype "passive"))
      (node (ref "R32") (pin "1") (pinfunction "1_1") (pintype "passive"))
      (node (ref "TL074CN-1") (pin "6") (pinfunction "2IN-_6") (pintype "input"))
    )
    (net (code "60") (name "Net-(TL074CN-1-2OUT)") (class "Default")
      (node (ref "R14") (pin "1") (pinfunction "1_1") (pintype "passive"))
      (node (ref "R32") (pin "2") (pinfunction "2_2") (pintype "passive"))
      (node (ref "TL074CN-1") (pin "7") (pinfunction "2OUT_7") (pintype "output"))
    )
    (net (code "61") (name "Net-(TL074CN-1-3IN-)") (class "Default")
      (node (ref "R33") (pin "2") (pinfunction "2_2") (pintype "passive"))
      (node (ref "R34") (pin "1") (pinfunction "1_1") (pintype "passive"))
      (node (ref "TL074CN-1") (pin "9") (pinfunction "3IN-_9") (pintype "input"))
    )
    (net (code "62") (name "Net-(TL074CN-1-3OUT)") (class "Default")
      (node (ref "R30") (pin "1") (pinfunction "1_1") (pintype "passive"))
      (node (ref "R33") (pin "1") (pinfunction "1_1") (pintype "passive"))
      (node (ref "TL074CN-1") (pin "8") (pinfunction "3OUT_8") (pintype "output"))
    )
    (net (code "63") (name "Net-(TL074CN-1-4IN-)") (class "Default")
      (node (ref "R35") (pin "1") (pinfunction "1_1") (pintype "passive"))
      (node (ref "R36") (pin "2") (pinfunction "2_2") (pintype "passive"))
      (node (ref "TL074CN-1") (pin "13") (pinfunction "4IN-_13") (pintype "input"))
    )
    (net (code "64") (name "Net-(TL074CN-1-4OUT)") (class "Default")
      (node (ref "R15") (pin "1") (pinfunction "1_1") (pintype "passive"))
      (node (ref "R36") (pin "1") (pinfunction "1_1") (pintype "passive"))
      (node (ref "TL074CN-1") (pin "14") (pinfunction "4OUT_14") (pintype "output"))
    )
    (net (code "65") (name "Net-(TL074CN-2-1IN-)") (class "Default")
      (node (ref "R22") (pin "2") (pinfunction "2_2") (pintype "passive"))
      (node (ref "R23") (pin "1") (pinfunction "1_1") (pintype "passive"))
      (node (ref "TL074CN-2") (pin "2") (pinfunction "1IN-_2") (pintype "input"))
    )
    (net (code "66") (name "Net-(TL074CN-2-1OUT)") (class "Default")
      (node (ref "R23") (pin "2") (pinfunction "2_2") (pintype "passive"))
      (node (ref "R24") (pin "1") (pinfunction "1_1") (pintype "passive"))
      (node (ref "TL074CN-2") (pin "1") (pinfunction "1OUT_1") (pintype "output"))
    )
    (net (code "67") (name "Net-(TL074CN-2-2IN-)") (class "Default")
      (node (ref "R16") (pin "2") (pinfunction "2_2") (pintype "passive"))
      (node (ref "R17") (pin "1") (pinfunction "1_1") (pintype "passive"))
      (node (ref "TL074CN-2") (pin "6") (pinfunction "2IN-_6") (pintype "input"))
    )
    (net (code "68") (name "Net-(TL074CN-2-2OUT)") (class "Default")
      (node (ref "R17") (pin "2") (pinfunction "2_2") (pintype "passive"))
      (node (ref "R18") (pin "1") (pinfunction "1_1") (pintype "passive"))
      (node (ref "TL074CN-2") (pin "7") (pinfunction "2OUT_7") (pintype "output"))
    )
    (net (code "69") (name "Net-(TL074CN-2-3IN-)") (class "Default")
      (node (ref "R19") (pin "2") (pinfunction "2_2") (pintype "passive"))
      (node (ref "R20") (pin "1") (pinfunction "1_1") (pintype "passive"))
      (node (ref "TL074CN-2") (pin "9") (pinfunction "3IN-_9") (pintype "input"))
    )
    (net (code "70") (name "Net-(TL074CN-2-3OUT)") (class "Default")
      (node (ref "R19") (pin "1") (pinfunction "1_1") (pintype "passive"))
      (node (ref "R21") (pin "1") (pinfunction "1_1") (pintype "passive"))
      (node (ref "TL074CN-2") (pin "8") (pinfunction "3OUT_8") (pintype "output"))
    )
    (net (code "71") (name "Net-(TL074CN-2-4IN-)") (class "Default")
      (node (ref "R25") (pin "1") (pinfunction "1_1") (pintype "passive"))
      (node (ref "R26") (pin "2") (pinfunction "2_2") (pintype "passive"))
      (node (ref "TL074CN-2") (pin "13") (pinfunction "4IN-_13") (pintype "input"))
    )
    (net (code "72") (name "Net-(TL074CN-2-4OUT)") (class "Default")
      (node (ref "R26") (pin "1") (pinfunction "1_1") (pintype "passive"))
      (node (ref "R27") (pin "1") (pinfunction "1_1") (pintype "passive"))
      (node (ref "TL074CN-2") (pin "14") (pinfunction "4OUT_14") (pintype "output"))
    )
    (net (code "73") (name "Net-(TR1-TIP)") (class "Default")
      (node (ref "R13") (pin "2") (pinfunction "2_2") (pintype "passive"))
      (node (ref "TR1") (pin "P$1_TIP") (pinfunction "TIP_P$1_TIP") (pintype "passive"))
    )
    (net (code "74") (name "Net-(TR2-TIP)") (class "Default")
      (node (ref "R14") (pin "2") (pinfunction "2_2") (pintype "passive"))
      (node (ref "TR2") (pin "P$1_TIP") (pinfunction "TIP_P$1_TIP") (pintype "passive"))
    )
    (net (code "75") (name "Net-(TR3-TIP)") (class "Default")
      (node (ref "R30") (pin "2") (pinfunction "2_2") (pintype "passive"))
      (node (ref "TR3") (pin "P$1_TIP") (pinfunction "TIP_P$1_TIP") (pintype "passive"))
    )
    (net (code "76") (name "Net-(TR4-TIP)") (class "Default")
      (node (ref "R15") (pin "2") (pinfunction "2_2") (pintype "passive"))
      (node (ref "TR4") (pin "P$1_TIP") (pinfunction "TIP_P$1_TIP") (pintype "passive"))
    )
    (net (code "77") (name "VCC") (class "Default")
      (node (ref "D1") (pin "C") (pinfunction "C_C") (pintype "passive"))
      (node (ref "TL074CN-1") (pin "4") (pinfunction "VCC+_4") (pintype "power_in"))
      (node (ref "TL074CN-2") (pin "4") (pinfunction "VCC+_4") (pintype "power_in"))
      (node (ref "U$2") (pin "IN") (pinfunction "IN_IN") (pintype "input"))
    )
    (net (code "78") (name "VSS") (class "Default")
      (node (ref "D2") (pin "A") (pinfunction "A_A") (pintype "passive"))
      (node (ref "TL074CN-1") (pin "11") (pinfunction "VCC-_11") (pintype "power_in"))
      (node (ref "TL074CN-2") (pin "11") (pinfunction "VCC-_11") (pintype "power_in"))
    )
    (net (code "79") (name "unconnected-(CV1-SWITCH-PadP$2_SWITCH)") (class "Default")
      (node (ref "CV1") (pin "P$2_SWITCH") (pinfunction "SWITCH_P$2_SWITCH") (pintype "passive"))
    )
    (net (code "80") (name "unconnected-(CV2-SWITCH-PadP$2_SWITCH)") (class "Default")
      (node (ref "CV2") (pin "P$2_SWITCH") (pinfunction "SWITCH_P$2_SWITCH") (pintype "passive"))
    )
    (net (code "81") (name "unconnected-(CV3-SWITCH-PadP$2_SWITCH)") (class "Default")
      (node (ref "CV3") (pin "P$2_SWITCH") (pinfunction "SWITCH_P$2_SWITCH") (pintype "passive"))
    )
    (net (code "82") (name "unconnected-(CV4-SWITCH-PadP$2_SWITCH)") (class "Default")
      (node (ref "CV4") (pin "P$2_SWITCH") (pinfunction "SWITCH_P$2_SWITCH") (pintype "passive"))
    )
    (net (code "83") (name "unconnected-(MCP4922-1-NC-Pad7)") (class "Default")
      (node (ref "MCP4922-1") (pin "7") (pinfunction "NC_7") (pintype "no_connect"))
    )
    (net (code "84") (name "unconnected-(MCP4922-1-NC_2-Pad2)") (class "Default")
      (node (ref "MCP4922-1") (pin "2") (pinfunction "NC_2_2") (pintype "no_connect"))
    )
    (net (code "85") (name "unconnected-(MCP4922-1-NC_3-Pad6)") (class "Default")
      (node (ref "MCP4922-1") (pin "6") (pinfunction "NC_3_6") (pintype "no_connect"))
    )
    (net (code "86") (name "unconnected-(MCP4922-2-NC-Pad7)") (class "Default")
      (node (ref "MCP4922-2") (pin "7") (pinfunction "NC_7") (pintype "no_connect"))
    )
    (net (code "87") (name "unconnected-(MCP4922-2-NC_2-Pad2)") (class "Default")
      (node (ref "MCP4922-2") (pin "2") (pinfunction "NC_2_2") (pintype "no_connect"))
    )
    (net (code "88") (name "unconnected-(MCP4922-2-NC_3-Pad6)") (class "Default")
      (node (ref "MCP4922-2") (pin "6") (pinfunction "NC_3_6") (pintype "no_connect"))
    )
    (net (code "89") (name "unconnected-(TR1-SWITCH-PadP$2_SWITCH)") (class "Default")
      (node (ref "TR1") (pin "P$2_SWITCH") (pinfunction "SWITCH_P$2_SWITCH") (pintype "passive"))
    )
    (net (code "90") (name "unconnected-(TR2-SWITCH-PadP$2_SWITCH)") (class "Default")
      (node (ref "TR2") (pin "P$2_SWITCH") (pinfunction "SWITCH_P$2_SWITCH") (pintype "passive"))
    )
    (net (code "91") (name "unconnected-(TR3-SWITCH-PadP$2_SWITCH)") (class "Default")
      (node (ref "TR3") (pin "P$2_SWITCH") (pinfunction "SWITCH_P$2_SWITCH") (pintype "passive"))
    )
    (net (code "92") (name "unconnected-(TR4-SWITCH-PadP$2_SWITCH)") (class "Default")
      (node (ref "TR4") (pin "P$2_SWITCH") (pinfunction "SWITCH_P$2_SWITCH") (pintype "passive"))
    )
    (net (code "93") (name "unconnected-(U$1-A21{slash}DAC0-Pad21{slash}DAC0)") (class "Default")
      (node (ref "U$1") (pin "21/DAC0") (pinfunction "A21/DAC0_21/DAC0") (pintype "bidirectional"))
    )
    (net (code "94") (name "unconnected-(U$1-Pad3V3)") (class "Default")
      (node (ref "U$1") (pin "3V3") (pinfunction "3V3_3V3") (pintype "bidirectional"))
    )
    (net (code "95") (name "unconnected-(U$1-Pad12{slash}MISO)") (class "Default")
      (node (ref "U$1") (pin "12/MISO") (pinfunction "12/MISO_12/MISO") (pintype "bidirectional"))
    )
    (net (code "96") (name "unconnected-(U$1-Pad32{slash}A13)") (class "Default")
      (node (ref "U$1") (pin "32/A13") (pinfunction "32/A13_32/A13") (pintype "bidirectional"))
    )
    (net (code "97") (name "unconnected-(U$1-Pad33{slash}A14)") (class "Default")
      (node (ref "U$1") (pin "33/A14") (pinfunction "33/A14_33/A14") (pintype "bidirectional"))
    )
    (net (code "98") (name "unconnected-(U$1-Pad34{slash}A15)") (class "Default")
      (node (ref "U$1") (pin "34/A15") (pinfunction "34/A15_34/A15") (pintype "bidirectional"))
    )
    (net (code "99") (name "unconnected-(U$1-Pad35{slash}A16)") (class "Default")
      (node (ref "U$1") (pin "35/A16") (pinfunction "35/A16_35/A16") (pintype "bidirectional"))
    )
    (net (code "100") (name "unconnected-(U$1-Pad36{slash}A17)") (class "Default")
      (node (ref "U$1") (pin "36/A17") (pinfunction "36/A17_36/A17") (pintype "bidirectional"))
    )
    (net (code "101") (name "unconnected-(U$1-Pad37{slash}A18)") (class "Default")
      (node (ref "U$1") (pin "37/A18") (pinfunction "37/A18_37/A18") (pintype "bidirectional"))
    )
    (net (code "102") (name "unconnected-(U$1-Pad38{slash}A19)") (class "Default")
      (node (ref "U$1") (pin "38/A19") (pinfunction "38/A19_38/A19") (pintype "bidirectional"))
    )
    (net (code "103") (name "unconnected-(U$1-Pad39{slash}A20)") (class "Default")
      (node (ref "U$1") (pin "39/A20") (pinfunction "39/A20_39/A20") (pintype "bidirectional"))
    )
    (net (code "104") (name "unconnected-(U$1-PadA10)") (class "Default")
      (node (ref "U$1") (pin "A10") (pinfunction "A10_A10") (pintype "bidirectional"))
    )
    (net (code "105") (name "unconnected-(U$1-PadA11)") (class "Default")
      (node (ref "U$1") (pin "A11") (pinfunction "A11_A11") (pintype "bidirectional"))
    )
    (net (code "106") (name "unconnected-(U$1-PadA22{slash}DAC1)") (class "Default")
      (node (ref "U$1") (pin "A22/DAC1") (pinfunction "A22/DAC1_A22/DAC1") (pintype "bidirectional"))
    )
    (net (code "107") (name "unconnected-(U$1-PadAGND)") (class "Default")
      (node (ref "U$1") (pin "AGND") (pinfunction "AGND_AGND") (pintype "bidirectional"))
    )
    (net (code "108") (name "unconnected-(U$1-PadAREF)") (class "Default")
      (node (ref "U$1") (pin "AREF") (pinfunction "AREF_AREF") (pintype "bidirectional"))
    )
    (net (code "109") (name "unconnected-(U$1-PadVUSB)") (class "Default")
      (node (ref "U$1") (pin "VUSB") (pinfunction "VUSB_VUSB") (pintype "bidirectional"))
    )
    (net (code "110") (name "unconnected-(U$4-PadINT)") (class "Default")
      (node (ref "U$4") (pin "INT") (pinfunction "INT_INT") (pintype "bidirectional"))
    )
  )
)
